# ToyCar.net
KiCad netlist of a schematic drawn in EasyEDA
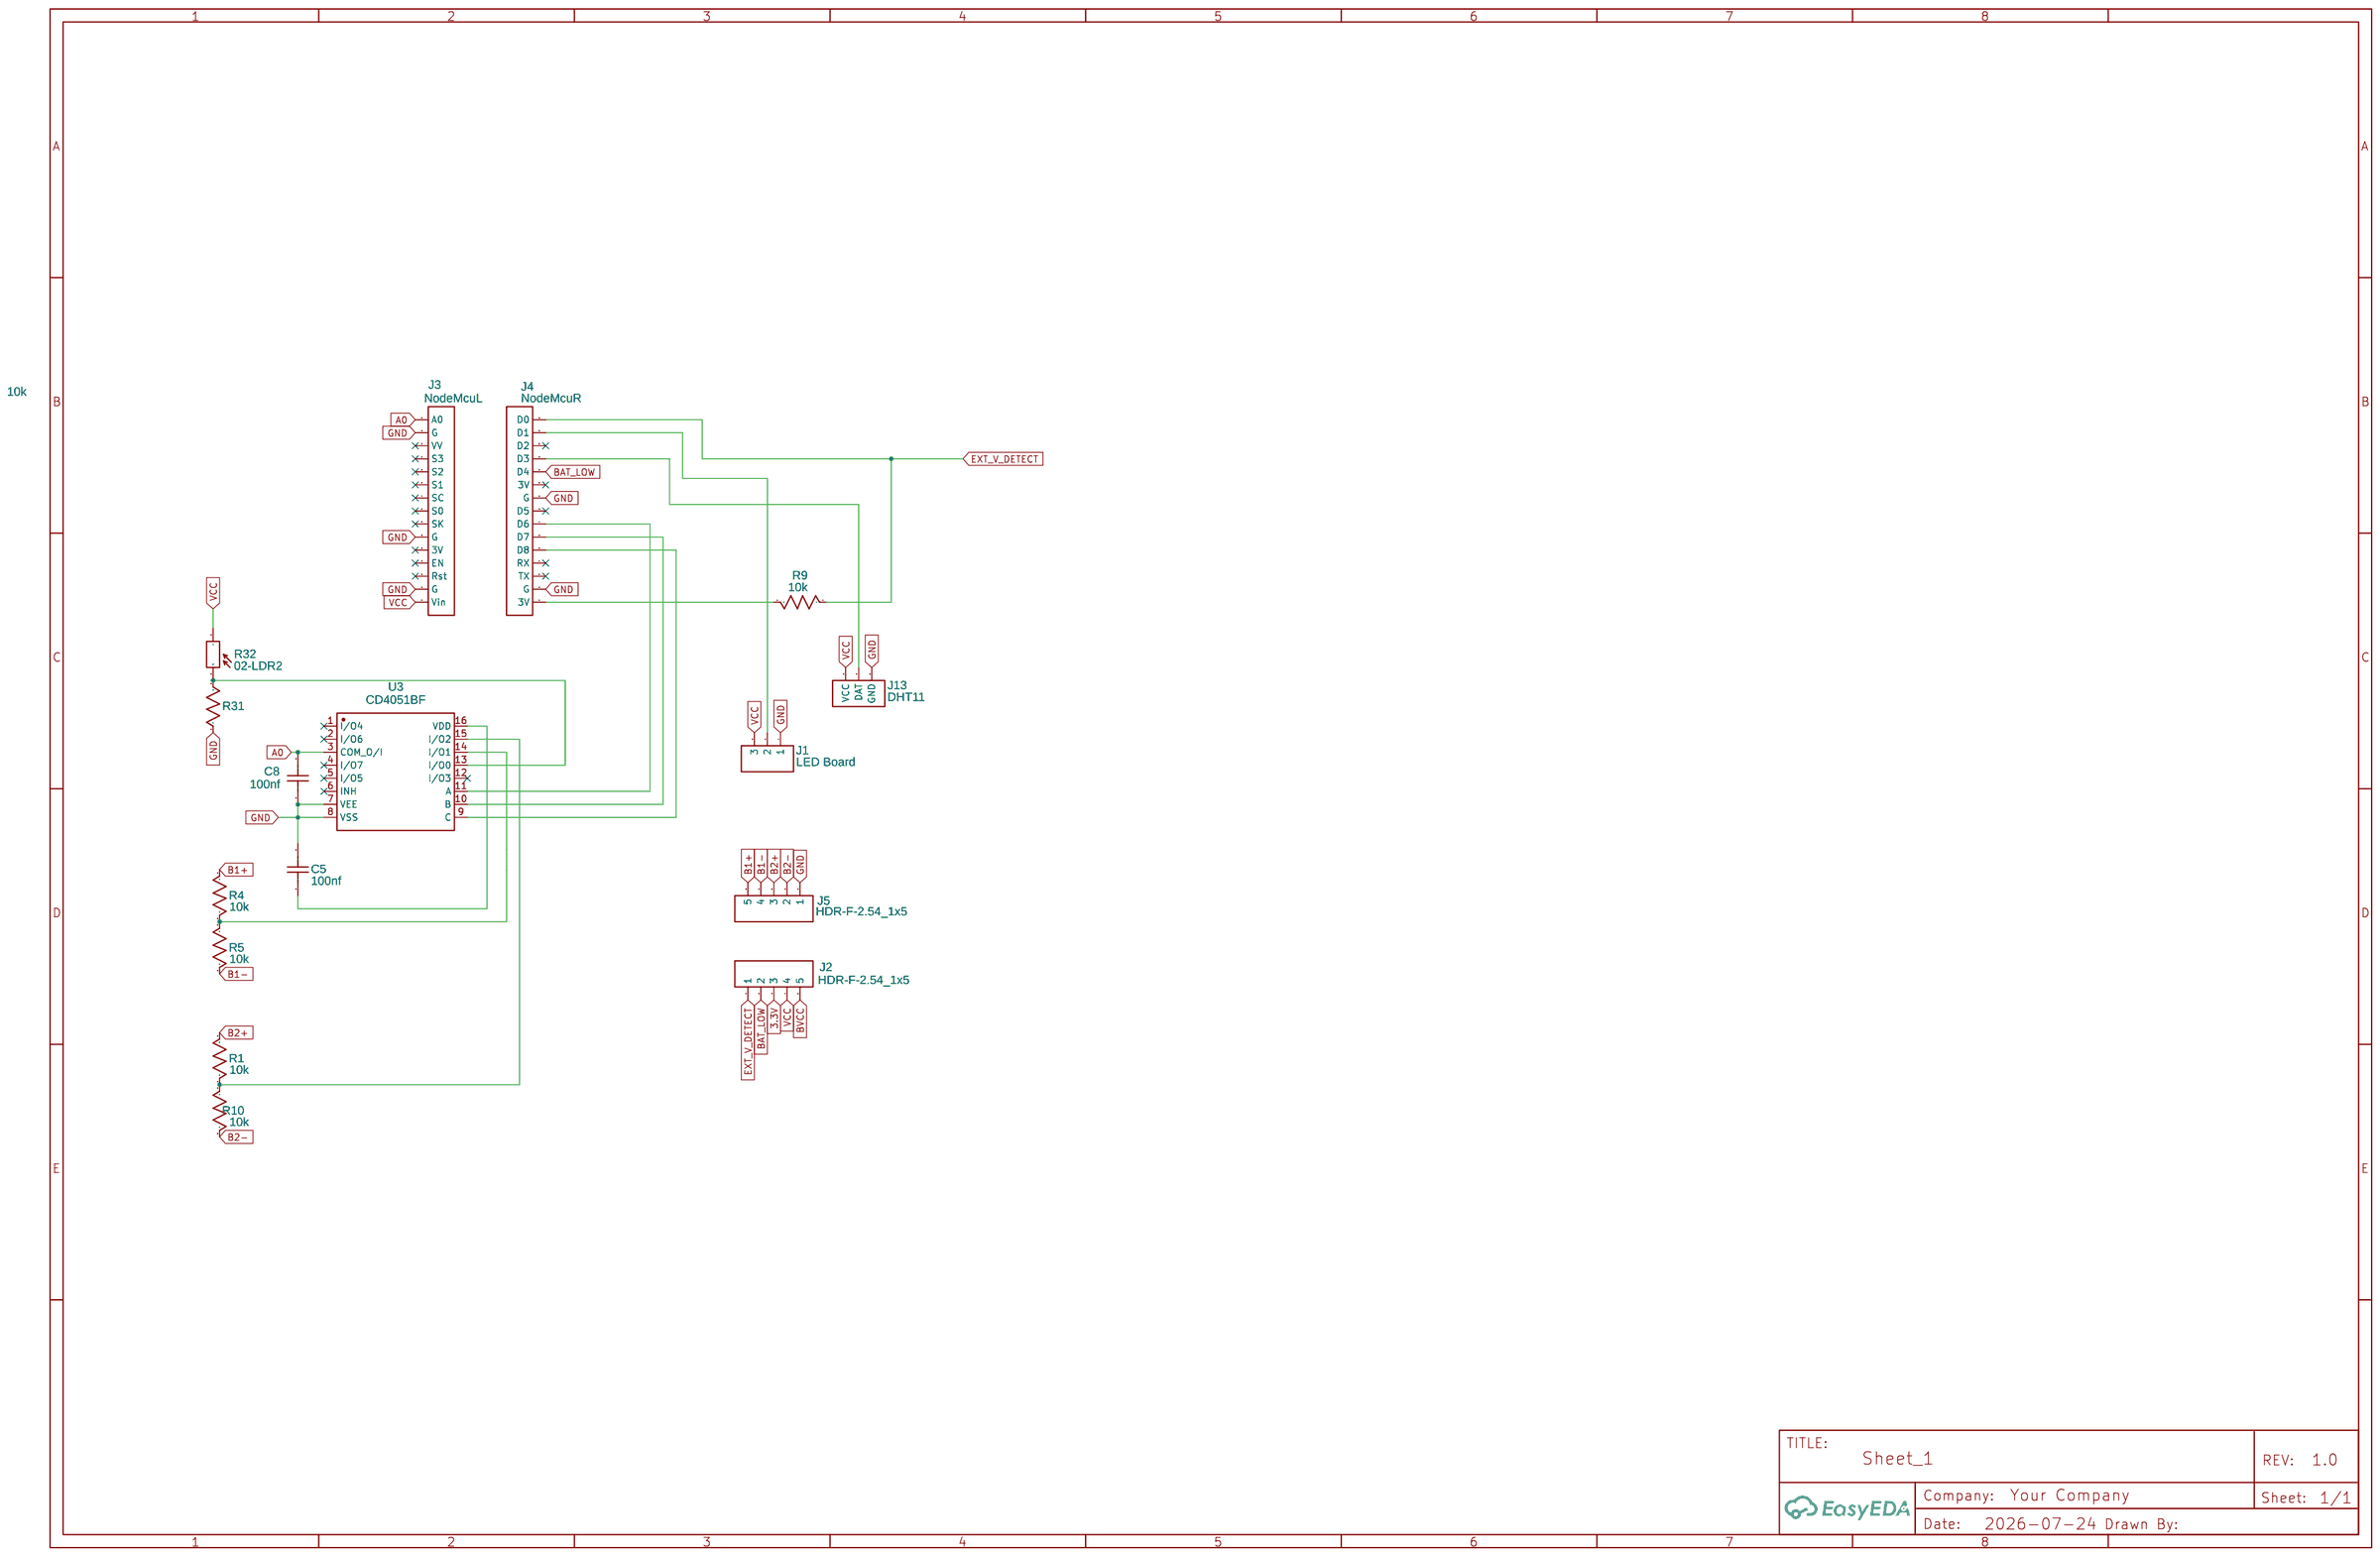
[diagram p0: schematic sheet]

(export (version "E")
  (design (tool "Eeschema 10.0.6"))
  (components
    (comp (ref "C5") (value "100nf") (libsource (lib "") (part "C_RAD-0.1_US")))
    (comp (ref "C8") (value "100nf") (libsource (lib "") (part "C_RAD-0.1_US")))
    (comp (ref "J1") (value "LED Board") (libsource (lib "") (part "HDR-M-2.54_1x3")))
    (comp (ref "J2") (value "HDR-F-2.54_1x5") (libsource (lib "") (part "HDR-M-2.54_1x5_1")))
    (comp (ref "J3") (value "NodeMcuL") (libsource (lib "") (part "HDR-M-2.54_1x15")))
    (comp (ref "J4") (value "NodeMcuR") (libsource (lib "") (part "HDR-M-2.54_1x15_1")))
    (comp (ref "J5") (value "HDR-F-2.54_1x5") (libsource (lib "") (part "HDR-M-2.54_1x5")))
    (comp (ref "J13") (value "DHT11") (libsource (lib "") (part "HDR-M-2.54_1x3_1")))
    (comp (ref "R1") (value "10k") (libsource (lib "") (part "R_AXIAL-0.3_US_1")))
    (comp (ref "R4") (value "10k") (libsource (lib "") (part "R_AXIAL-0.3_US_1")))
    (comp (ref "R5") (value "10k") (libsource (lib "") (part "R_AXIAL-0.3_US_1")))
    (comp (ref "R9") (value "10k") (libsource (lib "") (part "R_AXIAL-0.3_US_2")))
    (comp (ref "R10") (value "10k") (libsource (lib "") (part "R_AXIAL-0.3_US_1")))
    (comp (ref "R31") (value "10k") (libsource (lib "") (part "R_AXIAL-0.3_US")))
    (comp (ref "R32")
      (value "02-LDR2")
      (fields (field (name "Manufacturer") "NTE Electronics"))
      (libsource (lib "") (part "02-LDR2"))
    )
    (comp (ref "U3")
      (value "CD4051BF")
      (fields (field (name "Manufacturer") "TI(德州仪器)"))
      (libsource (lib "") (part "CD4051BF"))
    )
  )
  (nets
    (net (code "1") (name "3.3V") (class "Default")
      (node (ref "J2") (pin "3") (pinfunction "3_3") (pintype "unspecified"))
    )
    (net (code "2") (name "A0") (class "Default")
      (node (ref "C8") (pin "1") (pinfunction "1_1") (pintype "unspecified"))
      (node (ref "J3") (pin "1") (pinfunction "A0_1") (pintype "unspecified"))
      (node (ref "U3") (pin "3") (pinfunction "COM_O/I_3") (pintype "unspecified"))
    )
    (net (code "3") (name "B1+") (class "Default")
      (node (ref "J5") (pin "5") (pinfunction "5_5") (pintype "unspecified"))
      (node (ref "R4") (pin "1") (pinfunction "1_1") (pintype "unspecified"))
    )
    (net (code "4") (name "B1-") (class "Default")
      (node (ref "J5") (pin "4") (pinfunction "4_4") (pintype "unspecified"))
      (node (ref "R5") (pin "2") (pinfunction "2_2") (pintype "unspecified"))
    )
    (net (code "5") (name "B2+") (class "Default")
      (node (ref "J5") (pin "3") (pinfunction "3_3") (pintype "unspecified"))
      (node (ref "R1") (pin "1") (pinfunction "1_1") (pintype "unspecified"))
    )
    (net (code "6") (name "B2-") (class "Default")
      (node (ref "J5") (pin "2") (pinfunction "2_2") (pintype "unspecified"))
      (node (ref "R10") (pin "2") (pinfunction "2_2") (pintype "unspecified"))
    )
    (net (code "7") (name "BAT_LOW") (class "Default")
      (node (ref "J2") (pin "2") (pinfunction "2_2") (pintype "unspecified"))
      (node (ref "J4") (pin "11") (pinfunction "D4_11") (pintype "unspecified"))
    )
    (net (code "8") (name "BVCC") (class "Default")
      (node (ref "J2") (pin "5") (pinfunction "5_5") (pintype "unspecified"))
    )
    (net (code "9") (name "EXT_V_DETECT") (class "Default")
      (node (ref "J2") (pin "1") (pinfunction "1_1") (pintype "unspecified"))
      (node (ref "J4") (pin "15") (pinfunction "D0_15") (pintype "unspecified"))
      (node (ref "R9") (pin "1") (pinfunction "1_1") (pintype "unspecified"))
    )
    (net (code "10") (name "GND") (class "Default")
      (node (ref "C5") (pin "1") (pinfunction "1_1") (pintype "unspecified"))
      (node (ref "C8") (pin "2") (pinfunction "2_2") (pintype "unspecified"))
      (node (ref "J1") (pin "1") (pinfunction "1_1") (pintype "input"))
      (node (ref "J13") (pin "1") (pinfunction "GND_1") (pintype "input"))
      (node (ref "J3") (pin "10") (pinfunction "G_10") (pintype "unspecified"))
      (node (ref "J3") (pin "14") (pinfunction "G_14") (pintype "unspecified"))
      (node (ref "J3") (pin "2") (pinfunction "G_2") (pintype "unspecified"))
      (node (ref "J4") (pin "2") (pinfunction "G_2") (pintype "unspecified"))
      (node (ref "J4") (pin "9") (pinfunction "G_9") (pintype "unspecified"))
      (node (ref "J5") (pin "1") (pinfunction "1_1") (pintype "unspecified"))
      (node (ref "R31") (pin "1") (pinfunction "1_1") (pintype "unspecified"))
      (node (ref "U3") (pin "7") (pinfunction "VEE_7") (pintype "unspecified"))
      (node (ref "U3") (pin "8") (pinfunction "VSS_8") (pintype "unspecified"))
    )
    (net (code "11") (name "Net-(J4-3V-Pad1)") (class "Default")
      (node (ref "J4") (pin "1") (pinfunction "3V_1") (pintype "unspecified"))
      (node (ref "R9") (pin "2") (pinfunction "2_2") (pintype "unspecified"))
    )
    (net (code "12") (name "Net-(J4-D1)") (class "Default")
      (node (ref "J1") (pin "2") (pinfunction "2_2") (pintype "input"))
      (node (ref "J4") (pin "14") (pinfunction "D1_14") (pintype "unspecified"))
    )
    (net (code "13") (name "Net-(J4-D6)") (class "Default")
      (node (ref "J4") (pin "7") (pinfunction "D6_7") (pintype "unspecified"))
      (node (ref "U3") (pin "11") (pinfunction "A_11") (pintype "unspecified"))
    )
    (net (code "14") (name "Net-(J4-D7)") (class "Default")
      (node (ref "J4") (pin "6") (pinfunction "D7_6") (pintype "unspecified"))
      (node (ref "U3") (pin "10") (pinfunction "B_10") (pintype "unspecified"))
    )
    (net (code "15") (name "Net-(J4-D8)") (class "Default")
      (node (ref "J4") (pin "5") (pinfunction "D8_5") (pintype "unspecified"))
      (node (ref "U3") (pin "9") (pinfunction "C_9") (pintype "unspecified"))
    )
    (net (code "16") (name "Net-(J13-DAT)") (class "Default")
      (node (ref "J13") (pin "2") (pinfunction "DAT_2") (pintype "input"))
      (node (ref "J4") (pin "12") (pinfunction "D3_12") (pintype "unspecified"))
    )
    (net (code "17") (name "Net-(U3-I{slash}O0)") (class "Default")
      (node (ref "R31") (pin "2") (pinfunction "2_2") (pintype "unspecified"))
      (node (ref "R32") (pin "2") (pinfunction "2_2") (pintype "unspecified"))
      (node (ref "U3") (pin "13") (pinfunction "I/O0_13") (pintype "unspecified"))
    )
    (net (code "18") (name "Net-(U3-I{slash}O1)") (class "Default")
      (node (ref "R4") (pin "2") (pinfunction "2_2") (pintype "unspecified"))
      (node (ref "R5") (pin "1") (pinfunction "1_1") (pintype "unspecified"))
      (node (ref "U3") (pin "14") (pinfunction "I/O1_14") (pintype "unspecified"))
    )
    (net (code "19") (name "Net-(U3-I{slash}O2)") (class "Default")
      (node (ref "R1") (pin "2") (pinfunction "2_2") (pintype "unspecified"))
      (node (ref "R10") (pin "1") (pinfunction "1_1") (pintype "unspecified"))
      (node (ref "U3") (pin "15") (pinfunction "I/O2_15") (pintype "unspecified"))
    )
    (net (code "20") (name "Net-(U3-VDD)") (class "Default")
      (node (ref "C5") (pin "2") (pinfunction "2_2") (pintype "unspecified"))
      (node (ref "U3") (pin "16") (pinfunction "VDD_16") (pintype "unspecified"))
    )
    (net (code "21") (name "VCC") (class "Default")
      (node (ref "J1") (pin "3") (pinfunction "3_3") (pintype "input"))
      (node (ref "J13") (pin "3") (pinfunction "VCC_3") (pintype "input"))
      (node (ref "J2") (pin "4") (pinfunction "4_4") (pintype "unspecified"))
      (node (ref "J3") (pin "15") (pinfunction "Vin_15") (pintype "unspecified"))
      (node (ref "R32") (pin "1") (pinfunction "1_1") (pintype "unspecified"))
    )
    (net (code "22") (name "unconnected-(J3-3V-Pad11)") (class "Default")
      (node (ref "J3") (pin "11") (pinfunction "3V_11") (pintype "unspecified+no_connect"))
    )
    (net (code "23") (name "unconnected-(J3-EN-Pad12)") (class "Default")
      (node (ref "J3") (pin "12") (pinfunction "EN_12") (pintype "unspecified+no_connect"))
    )
    (net (code "24") (name "unconnected-(J3-Rst-Pad13)") (class "Default")
      (node (ref "J3") (pin "13") (pinfunction "Rst_13") (pintype "unspecified+no_connect"))
    )
    (net (code "25") (name "unconnected-(J3-S0-Pad8)") (class "Default")
      (node (ref "J3") (pin "8") (pinfunction "S0_8") (pintype "unspecified+no_connect"))
    )
    (net (code "26") (name "unconnected-(J3-S1-Pad6)") (class "Default")
      (node (ref "J3") (pin "6") (pinfunction "S1_6") (pintype "unspecified+no_connect"))
    )
    (net (code "27") (name "unconnected-(J3-S2-Pad5)") (class "Default")
      (node (ref "J3") (pin "5") (pinfunction "S2_5") (pintype "unspecified+no_connect"))
    )
    (net (code "28") (name "unconnected-(J3-S3-Pad4)") (class "Default")
      (node (ref "J3") (pin "4") (pinfunction "S3_4") (pintype "unspecified+no_connect"))
    )
    (net (code "29") (name "unconnected-(J3-SC-Pad7)") (class "Default")
      (node (ref "J3") (pin "7") (pinfunction "SC_7") (pintype "unspecified+no_connect"))
    )
    (net (code "30") (name "unconnected-(J3-SK-Pad9)") (class "Default")
      (node (ref "J3") (pin "9") (pinfunction "SK_9") (pintype "unspecified+no_connect"))
    )
    (net (code "31") (name "unconnected-(J3-VV-Pad3)") (class "Default")
      (node (ref "J3") (pin "3") (pinfunction "VV_3") (pintype "unspecified+no_connect"))
    )
    (net (code "32") (name "unconnected-(J4-3V-Pad10)") (class "Default")
      (node (ref "J4") (pin "10") (pinfunction "3V_10") (pintype "unspecified+no_connect"))
    )
    (net (code "33") (name "unconnected-(J4-D2-Pad13)") (class "Default")
      (node (ref "J4") (pin "13") (pinfunction "D2_13") (pintype "unspecified+no_connect"))
    )
    (net (code "34") (name "unconnected-(J4-D5-Pad8)") (class "Default")
      (node (ref "J4") (pin "8") (pinfunction "D5_8") (pintype "unspecified+no_connect"))
    )
    (net (code "35") (name "unconnected-(J4-RX-Pad4)") (class "Default")
      (node (ref "J4") (pin "4") (pinfunction "RX_4") (pintype "unspecified+no_connect"))
    )
    (net (code "36") (name "unconnected-(J4-TX-Pad3)") (class "Default")
      (node (ref "J4") (pin "3") (pinfunction "TX_3") (pintype "unspecified+no_connect"))
    )
    (net (code "37") (name "unconnected-(U3-INH-Pad6)") (class "Default")
      (node (ref "U3") (pin "6") (pinfunction "INH_6") (pintype "unspecified+no_connect"))
    )
    (net (code "38") (name "unconnected-(U3-I{slash}O3-Pad12)") (class "Default")
      (node (ref "U3") (pin "12") (pinfunction "I/O3_12") (pintype "unspecified+no_connect"))
    )
    (net (code "39") (name "unconnected-(U3-I{slash}O4-Pad1)") (class "Default")
      (node (ref "U3") (pin "1") (pinfunction "I/O4_1") (pintype "unspecified+no_connect"))
    )
    (net (code "40") (name "unconnected-(U3-I{slash}O5-Pad5)") (class "Default")
      (node (ref "U3") (pin "5") (pinfunction "I/O5_5") (pintype "unspecified+no_connect"))
    )
    (net (code "41") (name "unconnected-(U3-I{slash}O6-Pad2)") (class "Default")
      (node (ref "U3") (pin "2") (pinfunction "I/O6_2") (pintype "unspecified+no_connect"))
    )
    (net (code "42") (name "unconnected-(U3-I{slash}O7-Pad4)") (class "Default")
      (node (ref "U3") (pin "4") (pinfunction "I/O7_4") (pintype "unspecified+no_connect"))
    )
  )
)
